# main_board.net
KiCad netlist of a schematic drawn in EAGLE
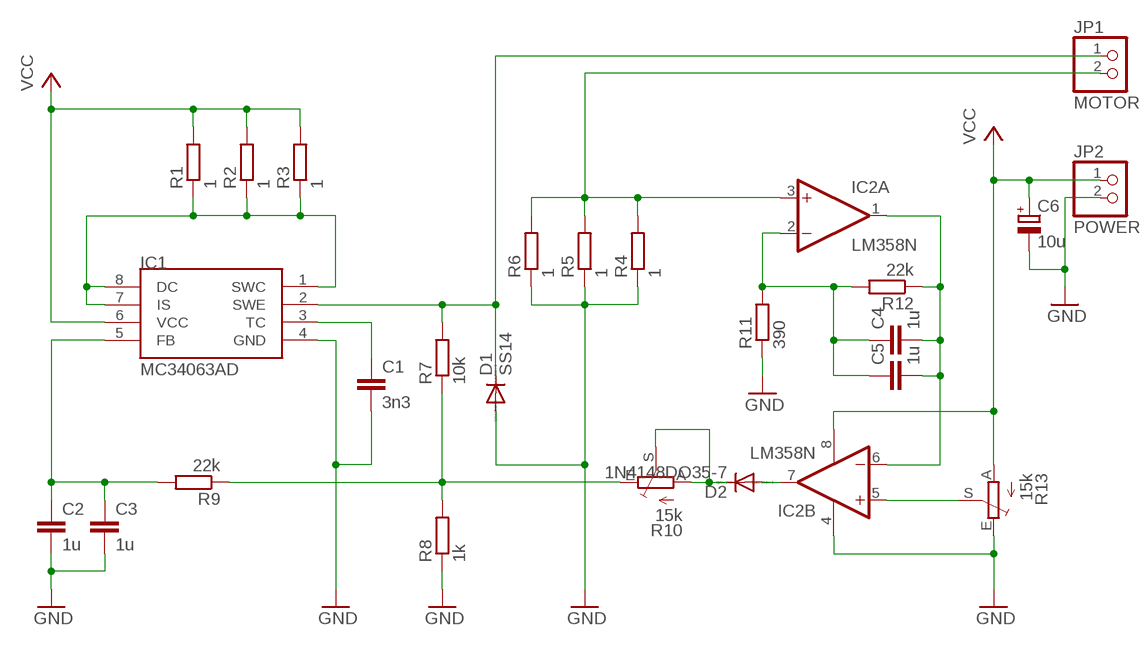
[diagram p0: schematic, sheet 1]

(export (version "E")
  (design (tool "Eeschema 10.0.6"))
  (components
    (comp (ref "C1")
      (value "3n3")
      (footprint "eagle-import:C0805")
      (libsource (lib "eagle-import") (part "C-EUC0805"))
    )
    (comp (ref "C2")
      (value "1u")
      (footprint "eagle-import:C0805")
      (libsource (lib "eagle-import") (part "C-EUC0805"))
    )
    (comp (ref "C3")
      (value "1u")
      (footprint "eagle-import:C0805")
      (libsource (lib "eagle-import") (part "C-EUC0805"))
    )
    (comp (ref "C4")
      (value "1u")
      (footprint "eagle-import:C0805")
      (libsource (lib "eagle-import") (part "C-EUC0805"))
    )
    (comp (ref "C5")
      (value "1u")
      (footprint "eagle-import:C0805")
      (libsource (lib "eagle-import") (part "C-EUC0805"))
    )
    (comp (ref "C6")
      (value "10u")
      (footprint "eagle-import:CT6032")
      (libsource (lib "eagle-import") (part "CPOL-EUCT6032"))
    )
    (comp (ref "D1")
      (value "SS14")
      (footprint "eagle-import:DO214AC")
      (libsource (lib "eagle-import") (part "DIODE-DO214AC"))
    )
    (comp (ref "D2")
      (value "1N4148DO35-7")
      (footprint "eagle-import:DO35-7")
      (libsource (lib "eagle-import") (part "1N4148DO35-7"))
    )
    (comp (ref "IC1")
      (value "MC34063AD")
      (footprint "eagle-import:SOIC8")
      (libsource (lib "eagle-import") (part "MC34063AD"))
    )
    (comp (ref "IC2")
      (value "LM358N")
      (footprint "eagle-import:DIL08")
      (libsource (lib "eagle-import") (part "LM358N"))
    )
    (comp (ref "JP1")
      (value "MOTOR")
      (footprint "eagle-import:1X02")
      (libsource (lib "eagle-import") (part "PINHD-1X2"))
    )
    (comp (ref "JP2")
      (value "POWER")
      (footprint "eagle-import:1X02")
      (libsource (lib "eagle-import") (part "PINHD-1X2"))
    )
    (comp (ref "R1")
      (value "1")
      (footprint "eagle-import:R0805")
      (libsource (lib "eagle-import") (part "R-EU_R0805"))
    )
    (comp (ref "R2")
      (value "1")
      (footprint "eagle-import:R0805")
      (libsource (lib "eagle-import") (part "R-EU_R0805"))
    )
    (comp (ref "R3")
      (value "1")
      (footprint "eagle-import:R0805")
      (libsource (lib "eagle-import") (part "R-EU_R0805"))
    )
    (comp (ref "R4")
      (value "1")
      (footprint "eagle-import:R0805")
      (libsource (lib "eagle-import") (part "R-EU_R0805"))
    )
    (comp (ref "R5")
      (value "1")
      (footprint "eagle-import:R0805")
      (libsource (lib "eagle-import") (part "R-EU_R0805"))
    )
    (comp (ref "R6")
      (value "1")
      (footprint "eagle-import:R0805")
      (libsource (lib "eagle-import") (part "R-EU_R0805"))
    )
    (comp (ref "R7")
      (value "10k")
      (footprint "eagle-import:R0805")
      (libsource (lib "eagle-import") (part "R-EU_R0805"))
    )
    (comp (ref "R8")
      (value "1k")
      (footprint "eagle-import:R0805")
      (libsource (lib "eagle-import") (part "R-EU_R0805"))
    )
    (comp (ref "R9")
      (value "22k")
      (footprint "eagle-import:R0805")
      (libsource (lib "eagle-import") (part "R-EU_R0805"))
    )
    (comp (ref "R10")
      (value "15k")
      (footprint "eagle-import:CA6V")
      (libsource (lib "eagle-import") (part "TRIM_EU-CA6V"))
    )
    (comp (ref "R11")
      (value "390")
      (footprint "eagle-import:R0805")
      (libsource (lib "eagle-import") (part "R-EU_R0805"))
    )
    (comp (ref "R12")
      (value "22k")
      (footprint "eagle-import:R0805")
      (libsource (lib "eagle-import") (part "R-EU_R0805"))
    )
    (comp (ref "R13")
      (value "15k")
      (footprint "eagle-import:CA6V")
      (libsource (lib "eagle-import") (part "TRIM_EU-CA6V"))
    )
  )
  (nets
    (net (code "1") (name "GND") (class "Default")
      (node (ref "C1") (pin "2") (pinfunction "2_2") (pintype "passive"))
      (node (ref "C2") (pin "2") (pinfunction "2_2") (pintype "passive"))
      (node (ref "C3") (pin "2") (pinfunction "2_2") (pintype "passive"))
      (node (ref "C6") (pin "-") (pinfunction "-_-") (pintype "passive"))
      (node (ref "D1") (pin "A") (pinfunction "A_A") (pintype "passive"))
      (node (ref "IC1") (pin "4") (pinfunction "GND_4") (pintype "passive"))
      (node (ref "IC2") (pin "4") (pinfunction "V-_4") (pintype "power_in"))
      (node (ref "JP2") (pin "2") (pinfunction "2_2") (pintype "passive"))
      (node (ref "R11") (pin "1") (pinfunction "1_1") (pintype "passive"))
      (node (ref "R13") (pin "E") (pinfunction "E_E") (pintype "passive"))
      (node (ref "R4") (pin "1") (pinfunction "1_1") (pintype "passive"))
      (node (ref "R5") (pin "1") (pinfunction "1_1") (pintype "passive"))
      (node (ref "R6") (pin "1") (pinfunction "1_1") (pintype "passive"))
      (node (ref "R8") (pin "1") (pinfunction "1_1") (pintype "passive"))
    )
    (net (code "2") (name "Net-(D2-PadC)") (class "Default")
      (node (ref "D2") (pin "C") (pinfunction "C_C") (pintype "passive"))
      (node (ref "R10") (pin "A") (pinfunction "A_A") (pintype "passive"))
      (node (ref "R10") (pin "S") (pinfunction "S_S") (pintype "passive"))
    )
    (net (code "3") (name "Net-(IC1-DC)") (class "Default")
      (node (ref "IC1") (pin "1") (pinfunction "SWC_1") (pintype "passive"))
      (node (ref "IC1") (pin "7") (pinfunction "IS_7") (pintype "passive"))
      (node (ref "IC1") (pin "8") (pinfunction "DC_8") (pintype "passive"))
      (node (ref "R1") (pin "1") (pinfunction "1_1") (pintype "passive"))
      (node (ref "R2") (pin "1") (pinfunction "1_1") (pintype "passive"))
      (node (ref "R3") (pin "1") (pinfunction "1_1") (pintype "passive"))
    )
    (net (code "4") (name "Net-(IC1-FB)") (class "Default")
      (node (ref "C2") (pin "1") (pinfunction "1_1") (pintype "passive"))
      (node (ref "C3") (pin "1") (pinfunction "1_1") (pintype "passive"))
      (node (ref "IC1") (pin "5") (pinfunction "FB_5") (pintype "passive"))
      (node (ref "R9") (pin "2") (pinfunction "2_2") (pintype "passive"))
    )
    (net (code "5") (name "Net-(IC1-SWE)") (class "Default")
      (node (ref "D1") (pin "C") (pinfunction "C_C") (pintype "passive"))
      (node (ref "IC1") (pin "2") (pinfunction "SWE_2") (pintype "passive"))
      (node (ref "JP1") (pin "1") (pinfunction "1_1") (pintype "passive"))
      (node (ref "R7") (pin "2") (pinfunction "2_2") (pintype "passive"))
    )
    (net (code "6") (name "Net-(IC1-TC)") (class "Default")
      (node (ref "C1") (pin "1") (pinfunction "1_1") (pintype "passive"))
      (node (ref "IC1") (pin "3") (pinfunction "TC_3") (pintype "passive"))
    )
    (net (code "7") (name "Net-(IC2A-+IN)") (class "Default")
      (node (ref "IC2") (pin "3") (pinfunction "+IN_3") (pintype "input"))
      (node (ref "JP1") (pin "2") (pinfunction "2_2") (pintype "passive"))
      (node (ref "R4") (pin "2") (pinfunction "2_2") (pintype "passive"))
      (node (ref "R5") (pin "2") (pinfunction "2_2") (pintype "passive"))
      (node (ref "R6") (pin "2") (pinfunction "2_2") (pintype "passive"))
    )
    (net (code "8") (name "Net-(IC2A--IN)") (class "Default")
      (node (ref "C4") (pin "1") (pinfunction "1_1") (pintype "passive"))
      (node (ref "C5") (pin "1") (pinfunction "1_1") (pintype "passive"))
      (node (ref "IC2") (pin "2") (pinfunction "-IN_2") (pintype "input"))
      (node (ref "R11") (pin "2") (pinfunction "2_2") (pintype "passive"))
      (node (ref "R12") (pin "2") (pinfunction "2_2") (pintype "passive"))
    )
    (net (code "9") (name "Net-(IC2A-OUT)") (class "Default")
      (node (ref "C4") (pin "2") (pinfunction "2_2") (pintype "passive"))
      (node (ref "C5") (pin "2") (pinfunction "2_2") (pintype "passive"))
      (node (ref "IC2") (pin "1") (pinfunction "OUT_1") (pintype "output"))
      (node (ref "IC2") (pin "6") (pinfunction "-IN_6") (pintype "input"))
      (node (ref "R12") (pin "1") (pinfunction "1_1") (pintype "passive"))
    )
    (net (code "10") (name "Net-(IC2B-+IN)") (class "Default")
      (node (ref "IC2") (pin "5") (pinfunction "+IN_5") (pintype "input"))
      (node (ref "R13") (pin "S") (pinfunction "S_S") (pintype "passive"))
    )
    (net (code "11") (name "Net-(IC2B-OUT)") (class "Default")
      (node (ref "D2") (pin "A") (pinfunction "A_A") (pintype "passive"))
      (node (ref "IC2") (pin "7") (pinfunction "OUT_7") (pintype "output"))
    )
    (net (code "12") (name "Net-(R10-PadE)") (class "Default")
      (node (ref "R10") (pin "E") (pinfunction "E_E") (pintype "passive"))
      (node (ref "R7") (pin "1") (pinfunction "1_1") (pintype "passive"))
      (node (ref "R8") (pin "2") (pinfunction "2_2") (pintype "passive"))
      (node (ref "R9") (pin "1") (pinfunction "1_1") (pintype "passive"))
    )
    (net (code "13") (name "VCC") (class "Default")
      (node (ref "C6") (pin "+") (pinfunction "+_+") (pintype "passive"))
      (node (ref "IC1") (pin "6") (pinfunction "VCC_6") (pintype "passive"))
      (node (ref "IC2") (pin "8") (pinfunction "V+_8") (pintype "power_in"))
      (node (ref "JP2") (pin "1") (pinfunction "1_1") (pintype "passive"))
      (node (ref "R1") (pin "2") (pinfunction "2_2") (pintype "passive"))
      (node (ref "R13") (pin "A") (pinfunction "A_A") (pintype "passive"))
      (node (ref "R2") (pin "2") (pinfunction "2_2") (pintype "passive"))
      (node (ref "R3") (pin "2") (pinfunction "2_2") (pintype "passive"))
    )
  )
)
